# 8ChannelIoTLEDDriver.net
KiCad netlist of a schematic drawn in EAGLE
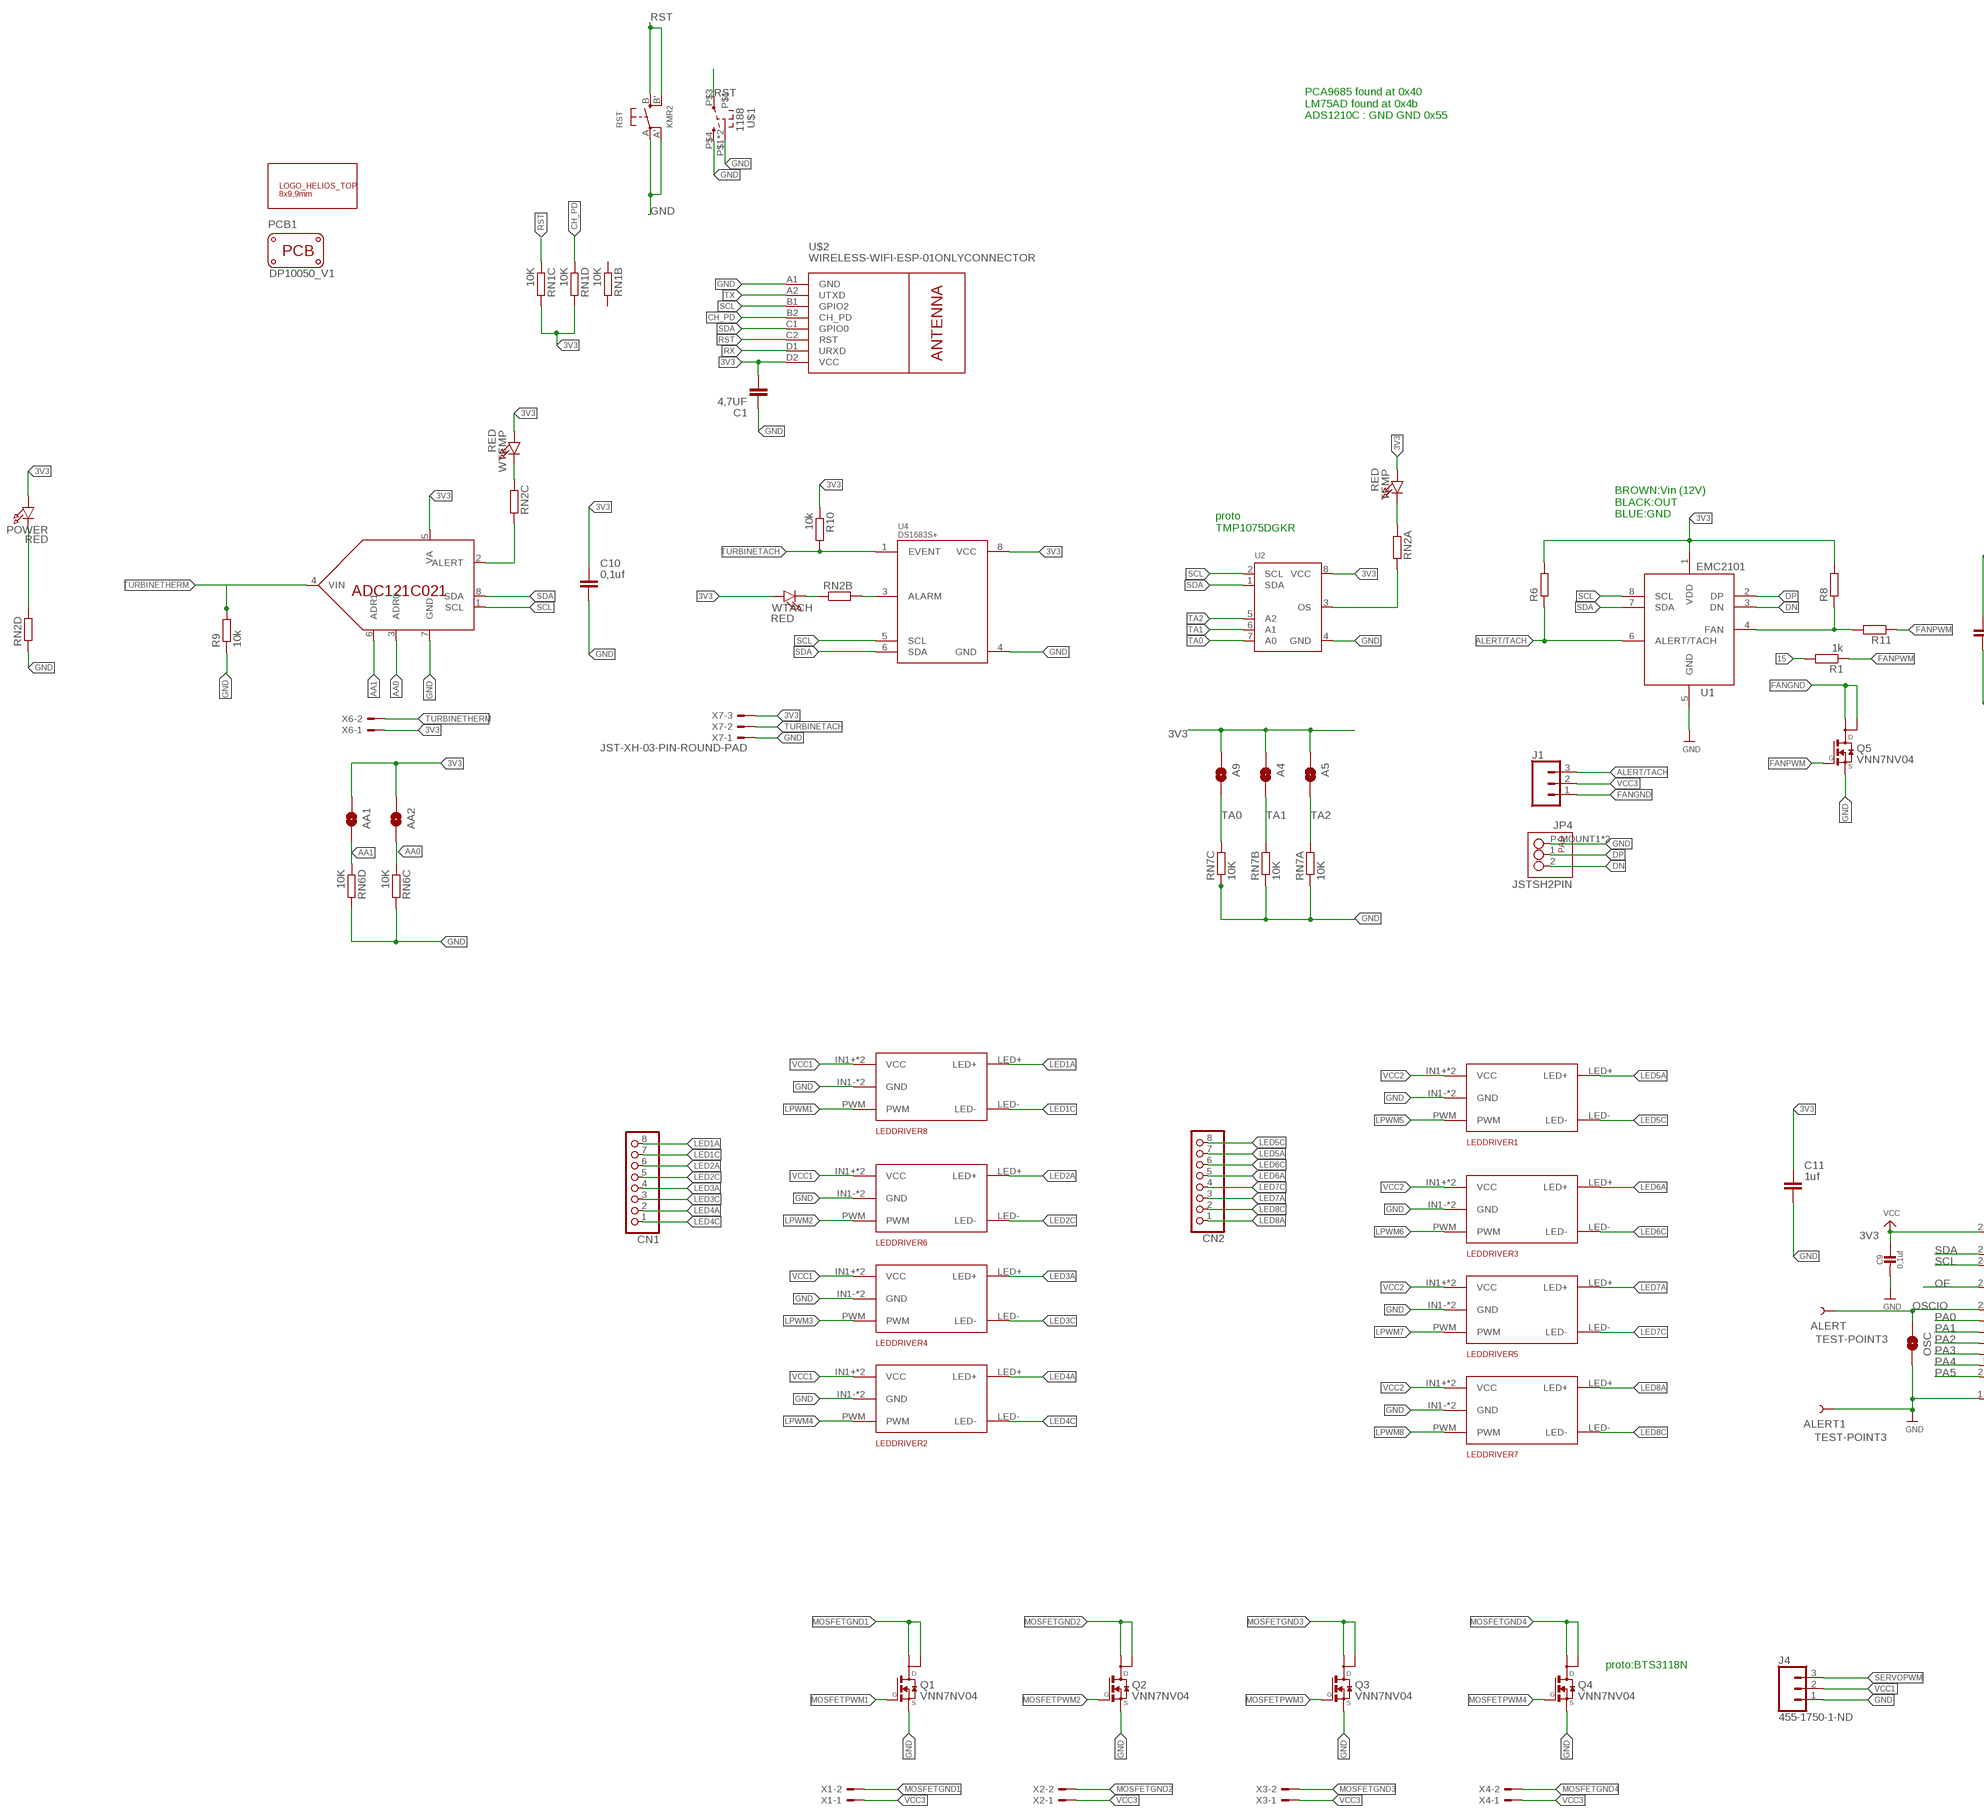
[diagram p0: schematic, sheet 1, part 1 of 2]
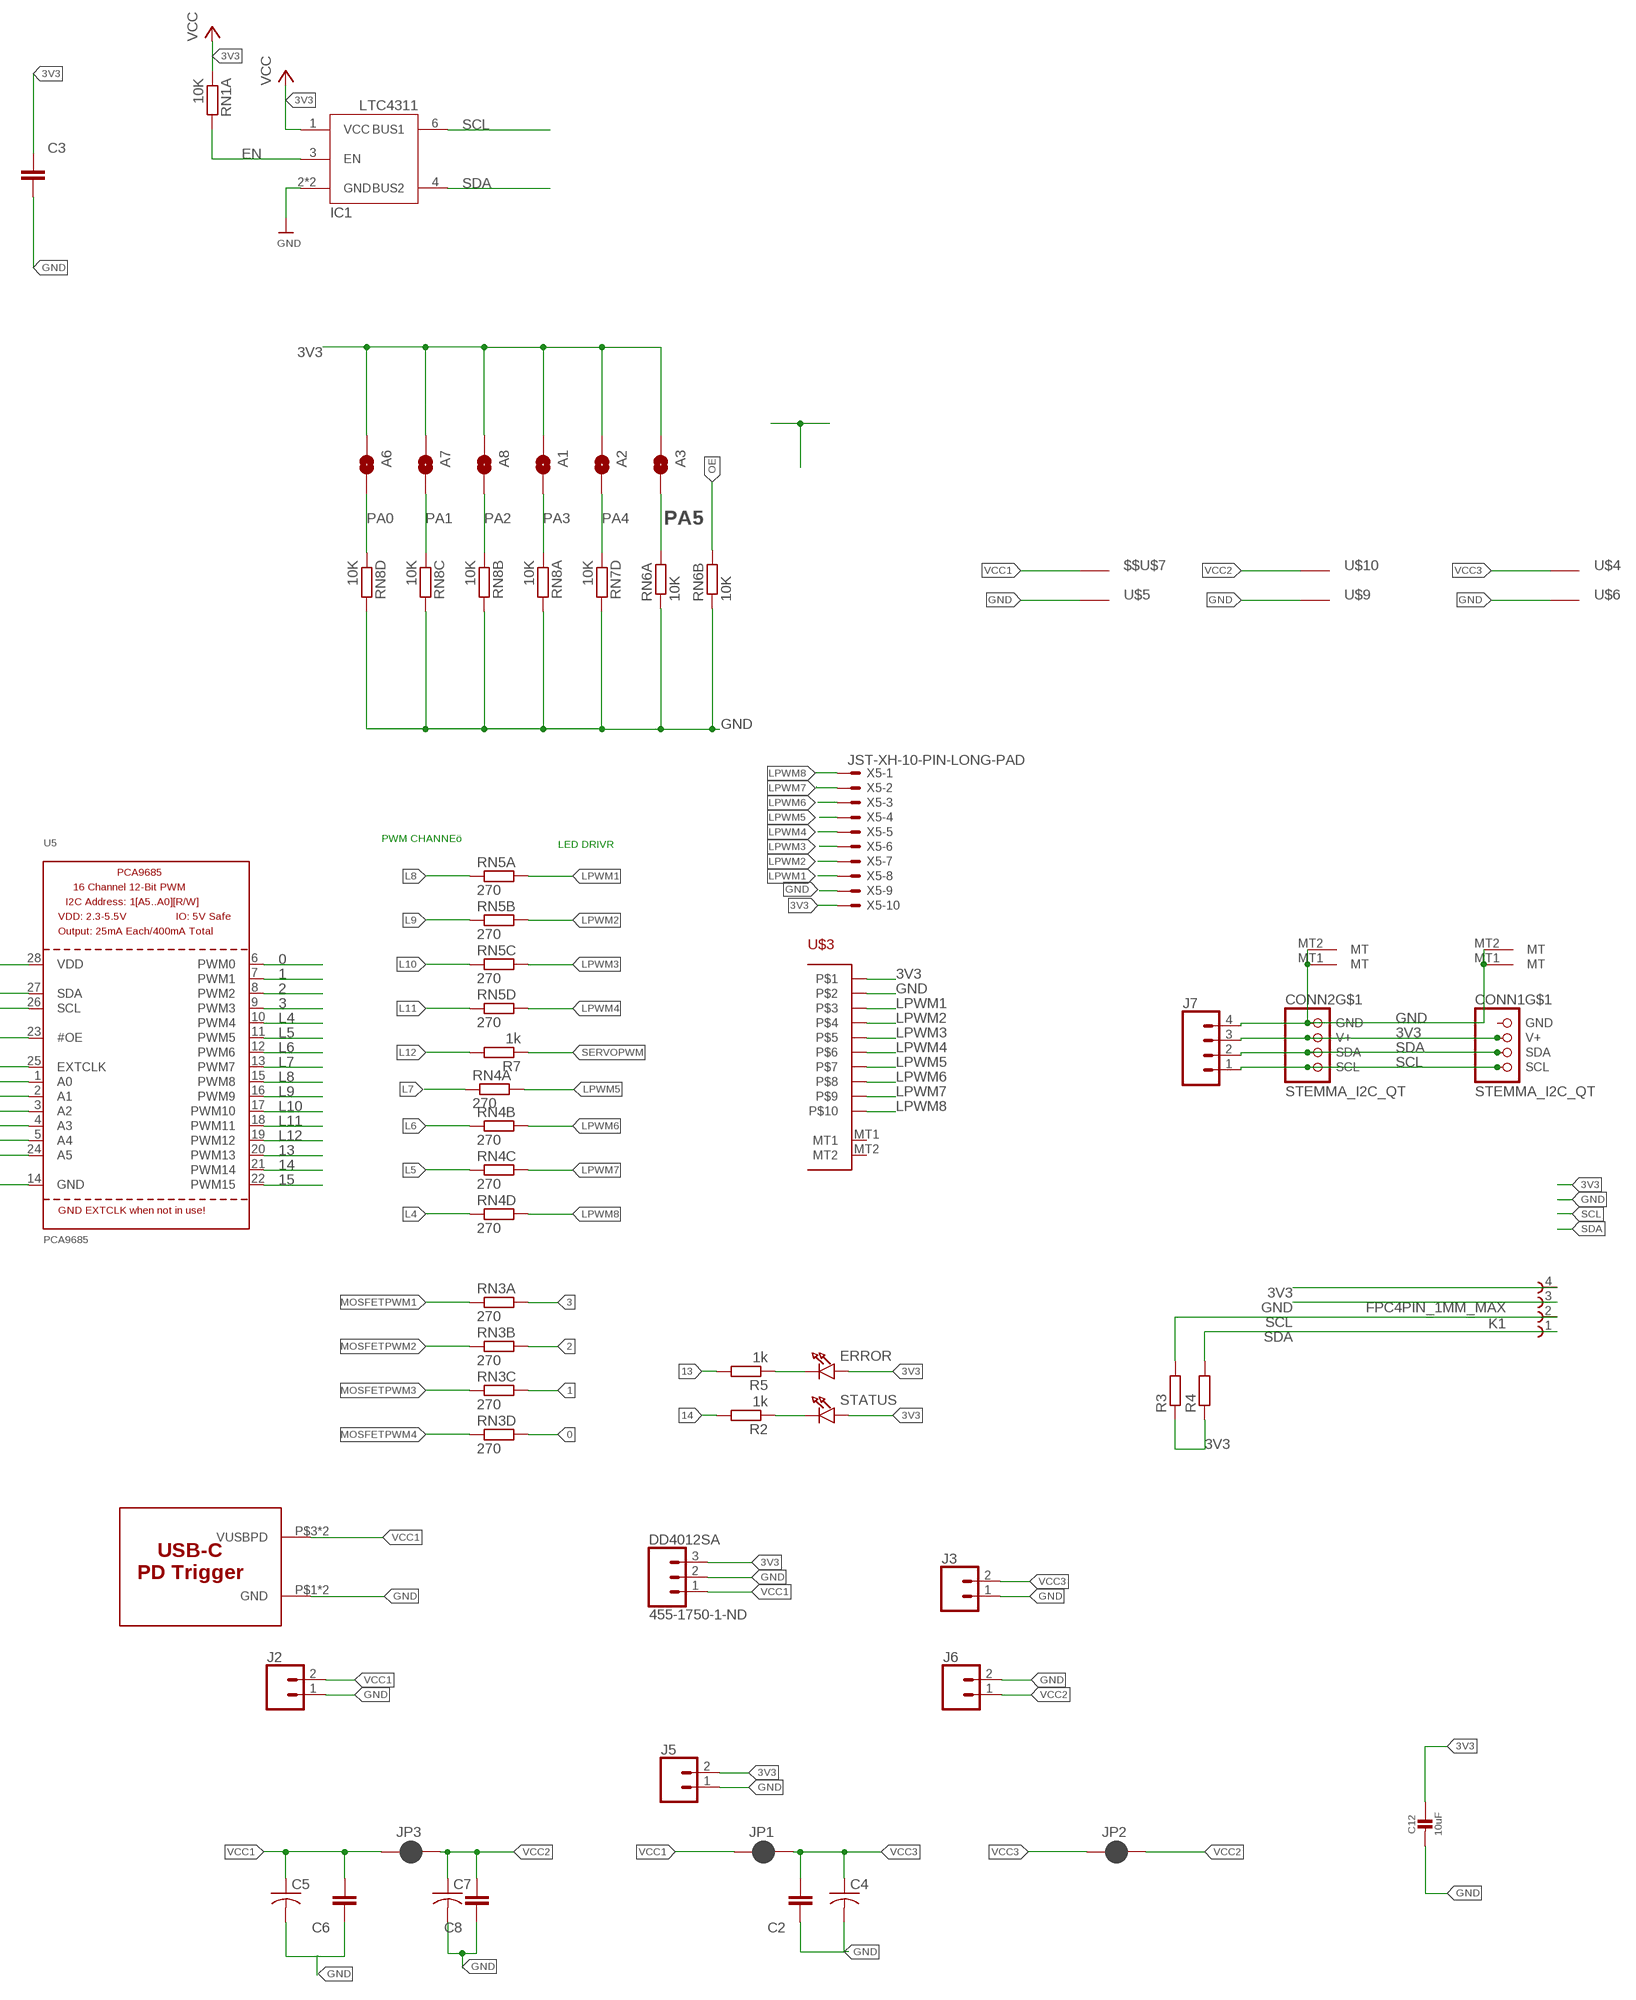
[diagram p1: schematic, sheet 1, part 2 of 2]

(export (version "E")
  (design (tool "Eeschema 10.0.6"))
  (components
    (comp (ref "$$U$7")
      (value "TESTHOOK")
      (footprint "eagle-import:TESTHOOK")
      (libsource (lib "eagle-import") (part "TESTHOOK"))
    )
    (comp (ref "A1")
      (value "JUMPER-SMT_2_NO_SILK")
      (footprint "eagle-import:SMT-JUMPER_2_NO_SILK")
      (libsource (lib "eagle-import") (part "JUMPER-SMT_2_NO_SILK"))
    )
    (comp (ref "A2")
      (value "JUMPER-SMT_2_NO_SILK")
      (footprint "eagle-import:SMT-JUMPER_2_NO_SILK")
      (libsource (lib "eagle-import") (part "JUMPER-SMT_2_NO_SILK"))
    )
    (comp (ref "A3")
      (value "JUMPER-SMT_2_NO_SILK")
      (footprint "eagle-import:SMT-JUMPER_2_NO_SILK")
      (libsource (lib "eagle-import") (part "JUMPER-SMT_2_NO_SILK"))
    )
    (comp (ref "A4")
      (value "JUMPER-SMT_2_NO_SILK")
      (footprint "eagle-import:SMT-JUMPER_2_NO_SILK")
      (libsource (lib "eagle-import") (part "JUMPER-SMT_2_NO_SILK"))
    )
    (comp (ref "A5")
      (value "JUMPER-SMT_2_NO_SILK")
      (footprint "eagle-import:SMT-JUMPER_2_NO_SILK")
      (libsource (lib "eagle-import") (part "JUMPER-SMT_2_NO_SILK"))
    )
    (comp (ref "A6")
      (value "JUMPER-SMT_2_NO_SILK")
      (footprint "eagle-import:SMT-JUMPER_2_NO_SILK")
      (libsource (lib "eagle-import") (part "JUMPER-SMT_2_NO_SILK"))
    )
    (comp (ref "A7")
      (value "JUMPER-SMT_2_NO_SILK")
      (footprint "eagle-import:SMT-JUMPER_2_NO_SILK")
      (libsource (lib "eagle-import") (part "JUMPER-SMT_2_NO_SILK"))
    )
    (comp (ref "A8")
      (value "JUMPER-SMT_2_NO_SILK")
      (footprint "eagle-import:SMT-JUMPER_2_NO_SILK")
      (libsource (lib "eagle-import") (part "JUMPER-SMT_2_NO_SILK"))
    )
    (comp (ref "A9")
      (value "JUMPER-SMT_2_NO_SILK")
      (footprint "eagle-import:SMT-JUMPER_2_NO_SILK")
      (libsource (lib "eagle-import") (part "JUMPER-SMT_2_NO_SILK"))
    )
    (comp (ref "AA1")
      (value "JUMPER-SMT_2_NO_SILK")
      (footprint "eagle-import:SMT-JUMPER_2_NO_SILK")
      (libsource (lib "eagle-import") (part "JUMPER-SMT_2_NO_SILK"))
    )
    (comp (ref "AA2")
      (value "JUMPER-SMT_2_NO_SILK")
      (footprint "eagle-import:SMT-JUMPER_2_NO_SILK")
      (libsource (lib "eagle-import") (part "JUMPER-SMT_2_NO_SILK"))
    )
    (comp (ref "ALERT")
      (value "TEST-POINT3")
      (footprint "eagle-import:PAD.03X.03")
      (libsource (lib "eagle-import") (part "TEST-POINT3"))
    )
    (comp (ref "ALERT1")
      (value "TEST-POINT3")
      (footprint "eagle-import:PAD.03X.03")
      (libsource (lib "eagle-import") (part "TEST-POINT3"))
    )
    (comp (ref "C1")
      (value "4,7UF")
      (footprint "eagle-import:C805")
      (libsource (lib "eagle-import") (part "CAPACITOR_NPOL-0805"))
    )
    (comp (ref "C2")
      (value "CAPACITOR_NPOL-0805")
      (footprint "eagle-import:C805")
      (libsource (lib "eagle-import") (part "CAPACITOR_NPOL-0805"))
    )
    (comp (ref "C3")
      (value "CAPACITOR_NPOL-0805")
      (footprint "eagle-import:C805")
      (libsource (lib "eagle-import") (part "CAPACITOR_NPOL-0805"))
    )
    (comp (ref "C4")
      (value "C-USC1210")
      (footprint "eagle-import:C1210")
      (libsource (lib "eagle-import") (part "C-USC1210"))
    )
    (comp (ref "C5")
      (value "C-USC1210")
      (footprint "eagle-import:C1210")
      (libsource (lib "eagle-import") (part "C-USC1210"))
    )
    (comp (ref "C6")
      (value "CAPACITOR_NPOL-0805")
      (footprint "eagle-import:C805")
      (libsource (lib "eagle-import") (part "CAPACITOR_NPOL-0805"))
    )
    (comp (ref "C7")
      (value "C-USC1210")
      (footprint "eagle-import:C1210")
      (libsource (lib "eagle-import") (part "C-USC1210"))
    )
    (comp (ref "C8")
      (value "CAPACITOR_NPOL-0805")
      (footprint "eagle-import:C805")
      (libsource (lib "eagle-import") (part "CAPACITOR_NPOL-0805"))
    )
    (comp (ref "C9")
      (value "0,1uf")
      (footprint "eagle-import:0805-NO")
      (libsource (lib "eagle-import") (part "CAP_CERAMIC0805-NOOUTLINE"))
    )
    (comp (ref "C10")
      (value "0,1uf")
      (footprint "eagle-import:C805")
      (libsource (lib "eagle-import") (part "CAPACITOR_NPOL-0805"))
    )
    (comp (ref "C11")
      (value "1uf")
      (footprint "eagle-import:C805")
      (libsource (lib "eagle-import") (part "CAPACITOR_NPOL-0805"))
    )
    (comp (ref "C12")
      (value "10uF")
      (footprint "eagle-import:0805-NO")
      (libsource (lib "eagle-import") (part "CAP_CERAMIC0805-NOOUTLINE"))
    )
    (comp (ref "CN1")
      (value "JST_8PIN")
      (footprint "eagle-import:JSTPH8")
      (libsource (lib "eagle-import") (part "JST_8PIN"))
    )
    (comp (ref "CN2")
      (value "JST_8PIN")
      (footprint "eagle-import:JSTPH8")
      (libsource (lib "eagle-import") (part "JST_8PIN"))
    )
    (comp (ref "CONN1")
      (value "STEMMA_I2C_QT")
      (footprint "eagle-import:JST_SH4")
      (libsource (lib "eagle-import") (part "STEMMA_I2C_QT"))
    )
    (comp (ref "CONN2")
      (value "STEMMA_I2C_QT")
      (footprint "eagle-import:JST_SH4")
      (libsource (lib "eagle-import") (part "STEMMA_I2C_QT"))
    )
    (comp (ref "DD4012SA")
      (value "455-1750-1-ND")
      (footprint "eagle-import:1X03")
      (libsource (lib "eagle-import") (part "CONN_03"))
    )
    (comp (ref "ERROR")
      (value "RED")
      (footprint "eagle-import:CHIPLED_0805")
      (libsource (lib "eagle-import") (part "LED0805"))
    )
    (comp (ref "IC1")
      (value "LTC4311_SC70")
      (footprint "eagle-import:SC70-6L")
      (libsource (lib "eagle-import") (part "LTC4311_SC70"))
    )
    (comp (ref "J1")
      (value "CONN_03POLAR")
      (footprint "eagle-import:MOLEX-1X3")
      (libsource (lib "eagle-import") (part "CONN_03POLAR"))
    )
    (comp (ref "J2")
      (value "CONN_02POLAR")
      (footprint "eagle-import:MOLEX-1X2")
      (libsource (lib "eagle-import") (part "CONN_02POLAR"))
    )
    (comp (ref "J3")
      (value "CONN_02POLAR")
      (footprint "eagle-import:MOLEX-1X2")
      (libsource (lib "eagle-import") (part "CONN_02POLAR"))
    )
    (comp (ref "J4")
      (value "455-1750-1-ND")
      (footprint "eagle-import:1X03")
      (libsource (lib "eagle-import") (part "CONN_03"))
    )
    (comp (ref "J5")
      (value "CONN_02POLAR")
      (footprint "eagle-import:MOLEX-1X2")
      (libsource (lib "eagle-import") (part "CONN_02POLAR"))
    )
    (comp (ref "J6")
      (value "CONN_023.5MM")
      (footprint "eagle-import:SCREWTERMINAL-3.5MM-2")
      (libsource (lib "eagle-import") (part "CONN_023.5MM"))
    )
    (comp (ref "J7")
      (value "CONN_04JST-PH-4-1.0MM")
      (footprint "eagle-import:JST-4-SMD-VERT-1.0MM")
      (libsource (lib "eagle-import") (part "CONN_04JST-PH-4-1.0MM"))
    )
    (comp (ref "JP1")
      (value "JUMPER-SMT_2_NC_PASTE_SILK")
      (footprint "eagle-import:SMT-JUMPER_2_NC_PASTE_SILK")
      (libsource (lib "eagle-import") (part "JUMPER-SMT_2_NC_PASTE_SILK"))
    )
    (comp (ref "JP2")
      (value "JUMPER-SMT_2_NC_PASTE_SILK")
      (footprint "eagle-import:SMT-JUMPER_2_NC_PASTE_SILK")
      (libsource (lib "eagle-import") (part "JUMPER-SMT_2_NC_PASTE_SILK"))
    )
    (comp (ref "JP3")
      (value "JUMPER-SMT_2_NC_PASTE_SILK")
      (footprint "eagle-import:SMT-JUMPER_2_NC_PASTE_SILK")
      (libsource (lib "eagle-import") (part "JUMPER-SMT_2_NC_PASTE_SILK"))
    )
    (comp (ref "JP4")
      (value "JSTSH2PIN")
      (footprint "eagle-import:SM02B-SRSS-TB")
      (libsource (lib "eagle-import") (part "JSTSH2PIN"))
    )
    (comp (ref "K1")
      (value "FPC4PIN_1MM_MAX")
      (footprint "eagle-import:FPC_CONN_DOC_4PIN_ENLARGED")
      (libsource (lib "eagle-import") (part "FPC4PIN_1MM_MAX"))
    )
    (comp (ref "LEDDRIVER1")
      (value "LEDDRIVERPT4115LONG")
      (footprint "eagle-import:7PINLONGLEDDRIVER")
      (libsource (lib "eagle-import") (part "LEDDRIVERPT4115LONG"))
    )
    (comp (ref "LEDDRIVER2")
      (value "LEDDRIVERPT4115LONG")
      (footprint "eagle-import:7PINLONGLEDDRIVER")
      (libsource (lib "eagle-import") (part "LEDDRIVERPT4115LONG"))
    )
    (comp (ref "LEDDRIVER3")
      (value "LEDDRIVERPT4115LONG")
      (footprint "eagle-import:7PINLONGLEDDRIVER")
      (libsource (lib "eagle-import") (part "LEDDRIVERPT4115LONG"))
    )
    (comp (ref "LEDDRIVER4")
      (value "LEDDRIVERPT4115LONG")
      (footprint "eagle-import:7PINLONGLEDDRIVER")
      (libsource (lib "eagle-import") (part "LEDDRIVERPT4115LONG"))
    )
    (comp (ref "LEDDRIVER5")
      (value "LEDDRIVERPT4115LONG")
      (footprint "eagle-import:7PINLONGLEDDRIVER")
      (libsource (lib "eagle-import") (part "LEDDRIVERPT4115LONG"))
    )
    (comp (ref "LEDDRIVER6")
      (value "LEDDRIVERPT4115LONG")
      (footprint "eagle-import:7PINLONGLEDDRIVER")
      (libsource (lib "eagle-import") (part "LEDDRIVERPT4115LONG"))
    )
    (comp (ref "LEDDRIVER7")
      (value "LEDDRIVERPT4115LONG")
      (footprint "eagle-import:7PINLONGLEDDRIVER")
      (libsource (lib "eagle-import") (part "LEDDRIVERPT4115LONG"))
    )
    (comp (ref "LEDDRIVER8")
      (value "LEDDRIVERPT4115LONG")
      (footprint "eagle-import:7PINLONGLEDDRIVER")
      (libsource (lib "eagle-import") (part "LEDDRIVERPT4115LONG"))
    )
    (comp (ref "OSC")
      (value "JUMPER-SMT_2_NO_SILK")
      (footprint "eagle-import:SMT-JUMPER_2_NO_SILK")
      (libsource (lib "eagle-import") (part "JUMPER-SMT_2_NO_SILK"))
    )
    (comp (ref "PCB1")
      (value "PCB_DP_RECTANGLE-50X100")
      (footprint "eagle-import:DP10050_V1")
      (fields (field (name "PCB_SIZE") "DP10050_V1"))
      (libsource (lib "eagle-import") (part "PCB_DP_RECTANGLE-50X100"))
    )
    (comp (ref "POWER")
      (value "RED")
      (footprint "eagle-import:CHIPLED_0805")
      (libsource (lib "eagle-import") (part "LED0805"))
    )
    (comp (ref "Q1")
      (value "VNN7NV04")
      (footprint "eagle-import:SOT223")
      (fields (field (name "MF") "STMicroelectronics"))
      (libsource (lib "eagle-import") (part "VNN7NV04"))
    )
    (comp (ref "Q2")
      (value "VNN7NV04")
      (footprint "eagle-import:SOT223")
      (fields (field (name "MF") "STMicroelectronics"))
      (libsource (lib "eagle-import") (part "VNN7NV04"))
    )
    (comp (ref "Q3")
      (value "VNN7NV04")
      (footprint "eagle-import:SOT223")
      (fields (field (name "MF") "STMicroelectronics"))
      (libsource (lib "eagle-import") (part "VNN7NV04"))
    )
    (comp (ref "Q4")
      (value "VNN7NV04")
      (footprint "eagle-import:SOT223")
      (fields (field (name "MF") "STMicroelectronics"))
      (libsource (lib "eagle-import") (part "VNN7NV04"))
    )
    (comp (ref "Q5")
      (value "VNN7NV04")
      (footprint "eagle-import:SOT223")
      (fields (field (name "MF") "STMicroelectronics"))
      (libsource (lib "eagle-import") (part "VNN7NV04"))
    )
    (comp (ref "R1")
      (value "1k")
      (footprint "eagle-import:R805")
      (libsource (lib "eagle-import") (part "RESISTOR-0805R805"))
    )
    (comp (ref "R2")
      (value "1k")
      (footprint "eagle-import:R805")
      (libsource (lib "eagle-import") (part "RESISTOR-0805R805"))
    )
    (comp (ref "R3")
      (value "RESISTORR805-0805")
      (footprint "eagle-import:R805")
      (libsource (lib "eagle-import") (part "RESISTOR-0805R805"))
    )
    (comp (ref "R4")
      (value "RESISTORR805-0805")
      (footprint "eagle-import:R805")
      (libsource (lib "eagle-import") (part "RESISTOR-0805R805"))
    )
    (comp (ref "R5")
      (value "1k")
      (footprint "eagle-import:R805")
      (libsource (lib "eagle-import") (part "RESISTOR-0805R805"))
    )
    (comp (ref "R6")
      (value "RESISTORR805-0805")
      (footprint "eagle-import:R805")
      (libsource (lib "eagle-import") (part "RESISTOR-0805R805"))
    )
    (comp (ref "R7")
      (value "1k")
      (footprint "eagle-import:R805")
      (libsource (lib "eagle-import") (part "RESISTOR-0805R805"))
    )
    (comp (ref "R8")
      (value "RESISTORR805-0805")
      (footprint "eagle-import:R805")
      (libsource (lib "eagle-import") (part "RESISTOR-0805R805"))
    )
    (comp (ref "R9")
      (value "10k")
      (footprint "eagle-import:R805")
      (libsource (lib "eagle-import") (part "RESISTOR-0805R805"))
    )
    (comp (ref "R10")
      (value "10k")
      (footprint "eagle-import:R805")
      (libsource (lib "eagle-import") (part "RESISTOR-0805R805"))
    )
    (comp (ref "R11")
      (value "RESISTORR805-0805")
      (footprint "eagle-import:R805")
      (libsource (lib "eagle-import") (part "RESISTOR-0805R805"))
    )
    (comp (ref "RN1")
      (value "10K")
      (footprint "eagle-import:RN8P-4R-CRA06S")
      (libsource (lib "eagle-import") (part "RESISTOR_ARRAY_4"))
    )
    (comp (ref "RN2")
      (value "RESISTOR_ARRAY_4")
      (footprint "eagle-import:RN8P-4R-CRA06S")
      (libsource (lib "eagle-import") (part "RESISTOR_ARRAY_4"))
    )
    (comp (ref "RN3")
      (value "270")
      (footprint "eagle-import:RN8P-4R-CRA06S")
      (libsource (lib "eagle-import") (part "RESISTOR_ARRAY_4"))
    )
    (comp (ref "RN4")
      (value "270")
      (footprint "eagle-import:RN8P-4R-CRA06S")
      (libsource (lib "eagle-import") (part "RESISTOR_ARRAY_4"))
    )
    (comp (ref "RN5")
      (value "270")
      (footprint "eagle-import:RN8P-4R-CRA06S")
      (libsource (lib "eagle-import") (part "RESISTOR_ARRAY_4"))
    )
    (comp (ref "RN6")
      (value "10K")
      (footprint "eagle-import:RN8P-4R-CRA06S")
      (libsource (lib "eagle-import") (part "RESISTOR_ARRAY_4"))
    )
    (comp (ref "RN7")
      (value "10K")
      (footprint "eagle-import:RN8P-4R-CRA06S")
      (libsource (lib "eagle-import") (part "RESISTOR_ARRAY_4"))
    )
    (comp (ref "RN8")
      (value "10K")
      (footprint "eagle-import:RN8P-4R-CRA06S")
      (libsource (lib "eagle-import") (part "RESISTOR_ARRAY_4"))
    )
    (comp (ref "RST")
      (value "KMR2")
      (footprint "eagle-import:BTN_KMR2_4.6X2.8")
      (libsource (lib "eagle-import") (part "SWITCH_TACT_SMT4.6X2.8"))
    )
    (comp (ref "STATUS")
      (value "RED")
      (footprint "eagle-import:CHIPLED_0805")
      (libsource (lib "eagle-import") (part "LED0805"))
    )
    (comp (ref "TEMP")
      (value "RED")
      (footprint "eagle-import:CHIPLED_0805")
      (libsource (lib "eagle-import") (part "LED0805"))
    )
    (comp (ref "U$1")
      (value "1188")
      (footprint "eagle-import:1188")
      (libsource (lib "eagle-import") (part "1188"))
    )
    (comp (ref "U$2")
      (value "WIRELESS-WIFI-ESP-01ONLYCONNECTOR")
      (footprint "eagle-import:WIRELESS-WIFI-ESP-01-ONLYBOTTOM")
      (libsource (lib "eagle-import") (part "WIRELESS-WIFI-ESP-01ONLYCONNECTOR"))
    )
    (comp (ref "U$3")
      (value "FPC-1.0X10")
      (footprint "eagle-import:FPC_1.0X10")
      (libsource (lib "eagle-import") (part "FPC-1.0X10"))
    )
    (comp (ref "U$4")
      (value "TESTHOOK")
      (footprint "eagle-import:TESTHOOK")
      (libsource (lib "eagle-import") (part "TESTHOOK"))
    )
    (comp (ref "U$5")
      (value "TESTHOOK")
      (footprint "eagle-import:TESTHOOK")
      (libsource (lib "eagle-import") (part "TESTHOOK"))
    )
    (comp (ref "U$6")
      (value "TESTHOOK")
      (footprint "eagle-import:TESTHOOK")
      (libsource (lib "eagle-import") (part "TESTHOOK"))
    )
    (comp (ref "U$8")
      (value "USB_PD_TRIGGER")
      (footprint "eagle-import:USB-PDTRIGGER")
      (libsource (lib "eagle-import") (part "USB_PD_TRIGGER"))
    )
    (comp (ref "U$9")
      (value "TESTHOOK")
      (footprint "eagle-import:TESTHOOK")
      (libsource (lib "eagle-import") (part "TESTHOOK"))
    )
    (comp (ref "U$10")
      (value "TESTHOOK")
      (footprint "eagle-import:TESTHOOK")
      (libsource (lib "eagle-import") (part "TESTHOOK"))
    )
    (comp (ref "U$11")
      (value "LOGOTOPHELIOS")
      (footprint "eagle-import:LOGOTOPHELIOS")
      (libsource (lib "eagle-import") (part "LOGOTOPHELIOS"))
    )
    (comp (ref "U1")
      (value "EMC2101-AZCL")
      (footprint "eagle-import:MSOP8_0.65MM")
      (libsource (lib "eagle-import") (part "EMC2101-AZCL"))
    )
    (comp (ref "U2")
      (value "TEMP_LM75B")
      (footprint "eagle-import:TSSOP8")
      (libsource (lib "eagle-import") (part "TEMP_LM75B"))
    )
    (comp (ref "U3")
      (value "ADC121C021")
      (footprint "eagle-import:MSOP08")
      (libsource (lib "eagle-import") (part "ADC121C021"))
    )
    (comp (ref "U4")
      (value "DS1683S+")
      (footprint "eagle-import:SOIC8-N_MC")
      (libsource (lib "eagle-import") (part "DS1683S+"))
    )
    (comp (ref "U5")
      (value "PCA9685")
      (footprint "eagle-import:TSSOP28")
      (libsource (lib "eagle-import") (part "PCA9685"))
    )
    (comp (ref "WTACH")
      (value "RED")
      (footprint "eagle-import:CHIPLED_0805")
      (libsource (lib "eagle-import") (part "LED0805"))
    )
    (comp (ref "WTEMP")
      (value "RED")
      (footprint "eagle-import:CHIPLED_0805")
      (libsource (lib "eagle-import") (part "LED0805"))
    )
    (comp (ref "X1")
      (value "JST-XH-02-PIN-ROUND-PAD")
      (footprint "eagle-import:JST-XH-02-PACKAGE-ROUND-PAD")
      (libsource (lib "eagle-import") (part "JST-XH-02-PIN-ROUND-PAD"))
    )
    (comp (ref "X2")
      (value "JST-XH-02-PIN-ROUND-PAD")
      (footprint "eagle-import:JST-XH-02-PACKAGE-ROUND-PAD")
      (libsource (lib "eagle-import") (part "JST-XH-02-PIN-ROUND-PAD"))
    )
    (comp (ref "X3")
      (value "JST-XH-02-PIN-ROUND-PAD")
      (footprint "eagle-import:JST-XH-02-PACKAGE-ROUND-PAD")
      (libsource (lib "eagle-import") (part "JST-XH-02-PIN-ROUND-PAD"))
    )
    (comp (ref "X4")
      (value "JST-XH-02-PIN-ROUND-PAD")
      (footprint "eagle-import:JST-XH-02-PACKAGE-ROUND-PAD")
      (libsource (lib "eagle-import") (part "JST-XH-02-PIN-ROUND-PAD"))
    )
    (comp (ref "X5")
      (value "JST-XH-10-PIN-LONG-PAD")
      (footprint "eagle-import:JST-XH-10-PACKAGE-LONG-PAD")
      (libsource (lib "eagle-import") (part "JST-XH-10-PIN-LONG-PAD"))
    )
    (comp (ref "X6")
      (value "JST-XH-02-PIN-ROUND-PAD")
      (footprint "eagle-import:JST-XH-02-PACKAGE-ROUND-PAD")
      (libsource (lib "eagle-import") (part "JST-XH-02-PIN-ROUND-PAD"))
    )
    (comp (ref "X7")
      (value "JST-XH-03-PIN-ROUND-PAD")
      (footprint "eagle-import:JST-XH-03-PACKAGE-ROUND-PAD")
      (libsource (lib "eagle-import") (part "JST-XH-03-PIN-ROUND-PAD"))
    )
  )
  (nets
    (net (code "1") (name "/EN") (class "Default")
      (node (ref "IC1") (pin "3") (pinfunction "EN_3") (pintype "input"))
      (node (ref "RN1") (pin "8") (pinfunction "2_8") (pintype "passive"))
    )
    (net (code "2") (name "/OSCIO") (class "Default")
      (node (ref "ALERT") (pin "P$1") (pinfunction "1_P$1") (pintype "bidirectional"))
      (node (ref "OSC") (pin "1") (pinfunction "1_1") (pintype "passive"))
      (node (ref "U5") (pin "25") (pinfunction "EXTCLK_25") (pintype "input"))
    )
    (net (code "3") (name "/PA0") (class "Default")
      (node (ref "A6") (pin "2") (pinfunction "2_2") (pintype "passive"))
      (node (ref "RN8") (pin "4") (pinfunction "1_4") (pintype "passive"))
      (node (ref "U5") (pin "1") (pinfunction "A0_1") (pintype "bidirectional"))
    )
    (net (code "4") (name "/PA1") (class "Default")
      (node (ref "A7") (pin "2") (pinfunction "2_2") (pintype "passive"))
      (node (ref "RN8") (pin "3") (pinfunction "1_3") (pintype "passive"))
      (node (ref "U5") (pin "2") (pinfunction "A1_2") (pintype "bidirectional"))
    )
    (net (code "5") (name "/PA2") (class "Default")
      (node (ref "A8") (pin "2") (pinfunction "2_2") (pintype "passive"))
      (node (ref "RN8") (pin "2") (pinfunction "1_2") (pintype "passive"))
      (node (ref "U5") (pin "3") (pinfunction "A2_3") (pintype "bidirectional"))
    )
    (net (code "6") (name "/PA3") (class "Default")
      (node (ref "A1") (pin "2") (pinfunction "2_2") (pintype "passive"))
      (node (ref "RN8") (pin "1") (pinfunction "1_1") (pintype "passive"))
      (node (ref "U5") (pin "4") (pinfunction "A3_4") (pintype "bidirectional"))
    )
    (net (code "7") (name "/PA4") (class "Default")
      (node (ref "A2") (pin "2") (pinfunction "2_2") (pintype "passive"))
      (node (ref "RN7") (pin "4") (pinfunction "1_4") (pintype "passive"))
      (node (ref "U5") (pin "5") (pinfunction "A4_5") (pintype "bidirectional"))
    )
    (net (code "8") (name "/PA5") (class "Default")
      (node (ref "A3") (pin "2") (pinfunction "2_2") (pintype "passive"))
      (node (ref "RN6") (pin "8") (pinfunction "2_8") (pintype "passive"))
      (node (ref "U5") (pin "24") (pinfunction "A5_24") (pintype "bidirectional"))
    )
    (net (code "9") (name "0") (class "Default")
      (node (ref "RN3") (pin "5") (pinfunction "2_5") (pintype "passive"))
      (node (ref "U5") (pin "6") (pinfunction "PWM0_6") (pintype "output"))
    )
    (net (code "10") (name "1") (class "Default")
      (node (ref "RN3") (pin "6") (pinfunction "2_6") (pintype "passive"))
      (node (ref "U5") (pin "7") (pinfunction "PWM1_7") (pintype "output"))
    )
    (net (code "11") (name "2") (class "Default")
      (node (ref "RN3") (pin "7") (pinfunction "2_7") (pintype "passive"))
      (node (ref "U5") (pin "8") (pinfunction "PWM2_8") (pintype "output"))
    )
    (net (code "12") (name "3") (class "Default")
      (node (ref "RN3") (pin "8") (pinfunction "2_8") (pintype "passive"))
      (node (ref "U5") (pin "9") (pinfunction "PWM3_9") (pintype "output"))
    )
    (net (code "13") (name "3V3") (class "Default")
      (node (ref "A1") (pin "1") (pinfunction "1_1") (pintype "passive"))
      (node (ref "A2") (pin "1") (pinfunction "1_1") (pintype "passive"))
      (node (ref "A3") (pin "1") (pinfunction "1_1") (pintype "passive"))
      (node (ref "A4") (pin "1") (pinfunction "1_1") (pintype "passive"))
      (node (ref "A5") (pin "1") (pinfunction "1_1") (pintype "passive"))
      (node (ref "A6") (pin "1") (pinfunction "1_1") (pintype "passive"))
      (node (ref "A7") (pin "1") (pinfunction "1_1") (pintype "passive"))
      (node (ref "A8") (pin "1") (pinfunction "1_1") (pintype "passive"))
      (node (ref "A9") (pin "1") (pinfunction "1_1") (pintype "passive"))
      (node (ref "AA1") (pin "1") (pinfunction "1_1") (pintype "passive"))
      (node (ref "AA2") (pin "1") (pinfunction "1_1") (pintype "passive"))
      (node (ref "C1") (pin "2") (pinfunction "2_2") (pintype "passive"))
      (node (ref "C10") (pin "1") (pinfunction "1_1") (pintype "passive"))
      (node (ref "C11") (pin "1") (pinfunction "1_1") (pintype "passive"))
      (node (ref "C12") (pin "1") (pinfunction "1_1") (pintype "passive"))
      (node (ref "C3") (pin "1") (pinfunction "1_1") (pintype "passive"))
      (node (ref "C9") (pin "1") (pinfunction "1_1") (pintype "passive"))
      (node (ref "CONN1") (pin "2") (pinfunction "V+_2") (pintype "passive"))
      (node (ref "CONN2") (pin "2") (pinfunction "V+_2") (pintype "passive"))
      (node (ref "DD4012SA") (pin "3") (pinfunction "3_3") (pintype "passive"))
      (node (ref "ERROR") (pin "A") (pinfunction "A_A") (pintype "passive"))
      (node (ref "IC1") (pin "1") (pinfunction "VCC_1") (pintype "power_in"))
      (node (ref "J5") (pin "2") (pinfunction "2_2") (pintype "passive"))
      (node (ref "J7") (pin "3") (pinfunction "3_3") (pintype "passive"))
      (node (ref "K1") (pin "4") (pinfunction "4_4") (pintype "passive"))
      (node (ref "POWER") (pin "A") (pinfunction "A_A") (pintype "passive"))
      (node (ref "R10") (pin "1") (pinfunction "1_1") (pintype "passive"))
      (node (ref "R3") (pin "1") (pinfunction "1_1") (pintype "passive"))
      (node (ref "R4") (pin "1") (pinfunction "1_1") (pintype "passive"))
      (node (ref "R6") (pin "2") (pinfunction "2_2") (pintype "passive"))
      (node (ref "R8") (pin "2") (pinfunction "2_2") (pintype "passive"))
      (node (ref "RN1") (pin "1") (pinfunction "1_1") (pintype "passive"))
      (node (ref "RN1") (pin "5") (pinfunction "2_5") (pintype "passive"))
      (node (ref "RN1") (pin "6") (pinfunction "2_6") (pintype "passive"))
      (node (ref "STATUS") (pin "A") (pinfunction "A_A") (pintype "passive"))
      (node (ref "TEMP") (pin "A") (pinfunction "A_A") (pintype "passive"))
      (node (ref "U$2") (pin "D2") (pinfunction "VCC_D2") (pintype "power_in"))
      (node (ref "U$3") (pin "1") (pinfunction "P$1_1") (pintype "bidirectional"))
      (node (ref "U1") (pin "1") (pinfunction "VDD_1") (pintype "power_in"))
      (node (ref "U2") (pin "8") (pinfunction "VCC_8") (pintype "power_in"))
      (node (ref "U3") (pin "5") (pinfunction "VA_5") (pintype "power_in"))
      (node (ref "U4") (pin "8") (pinfunction "VCC_8") (pintype "bidirectional"))
      (node (ref "U5") (pin "28") (pinfunction "VDD_28") (pintype "power_in"))
      (node (ref "WTACH") (pin "A") (pinfunction "A_A") (pintype "passive"))
      (node (ref "WTEMP") (pin "A") (pinfunction "A_A") (pintype "passive"))
      (node (ref "X5") (pin "10") (pinfunction "S_10") (pintype "passive"))
      (node (ref "X6") (pin "1") (pinfunction "S_1") (pintype "passive"))
      (node (ref "X7") (pin "3") (pinfunction "S_3") (pintype "passive"))
    )
    (net (code "14") (name "13") (class "Default")
      (node (ref "R5") (pin "2") (pinfunction "2_2") (pintype "passive"))
      (node (ref "U5") (pin "20") (pinfunction "PWM13_20") (pintype "output"))
    )
    (net (code "15") (name "14") (class "Default")
      (node (ref "R2") (pin "2") (pinfunction "2_2") (pintype "passive"))
      (node (ref "U5") (pin "21") (pinfunction "PWM14_21") (pintype "output"))
    )
    (net (code "16") (name "15") (class "Default")
      (node (ref "R1") (pin "2") (pinfunction "2_2") (pintype "passive"))
      (node (ref "U5") (pin "22") (pinfunction "PWM15_22") (pintype "output"))
    )
    (net (code "17") (name "AA0") (class "Default")
      (node (ref "AA2") (pin "2") (pinfunction "2_2") (pintype "passive"))
      (node (ref "RN6") (pin "3") (pinfunction "1_3") (pintype "passive"))
      (node (ref "U3") (pin "3") (pinfunction "ADR0_3") (pintype "input"))
    )
    (net (code "18") (name "AA1") (class "Default")
      (node (ref "AA1") (pin "2") (pinfunction "2_2") (pintype "passive"))
      (node (ref "RN6") (pin "4") (pinfunction "1_4") (pintype "passive"))
      (node (ref "U3") (pin "6") (pinfunction "ADR1_6") (pintype "input"))
    )
    (net (code "19") (name "ALERT{slash}TACH") (class "Default")
      (node (ref "J1") (pin "3") (pinfunction "3_3") (pintype "passive"))
      (node (ref "R6") (pin "1") (pinfunction "1_1") (pintype "passive"))
      (node (ref "U1") (pin "6") (pinfunction "ALERT/TACH_6") (pintype "bidirectional"))
    )
    (net (code "20") (name "CH_PD") (class "Default")
      (node (ref "RN1") (pin "4") (pinfunction "1_4") (pintype "passive"))
      (node (ref "U$2") (pin "B2") (pinfunction "CH_PD_B2") (pintype "bidirectional"))
    )
    (net (code "21") (name "DN") (class "Default")
      (node (ref "JP4") (pin "2") (pinfunction "P$2_2") (pintype "bidirectional"))
      (node (ref "U1") (pin "3") (pinfunction "DN_3") (pintype "input"))
    )
    (net (code "22") (name "DP") (class "Default")
      (node (ref "JP4") (pin "1") (pinfunction "P$1_1") (pintype "bidirectional"))
      (node (ref "U1") (pin "2") (pinfunction "DP_2") (pintype "input"))
    )
    (net (code "23") (name "FANGND") (class "Default")
      (node (ref "J1") (pin "1") (pinfunction "1_1") (pintype "passive"))
      (node (ref "Q5") (pin "2") (pinfunction "D_2") (pintype "passive"))
      (node (ref "Q5") (pin "4") (pinfunction "D2_4") (pintype "passive"))
    )
    (net (code "24") (name "FANPWM") (class "Default")
      (node (ref "Q5") (pin "1") (pinfunction "G_1") (pintype "passive"))
      (node (ref "R1") (pin "1") (pinfunction "1_1") (pintype "passive"))
      (node (ref "R11") (pin "1") (pinfunction "1_1") (pintype "passive"))
    )
    (net (code "25") (name "GND") (class "Default")
      (node (ref "ALERT1") (pin "P$1") (pinfunction "1_P$1") (pintype "bidirectional"))
      (node (ref "C1") (pin "1") (pinfunction "1_1") (pintype "passive"))
      (node (ref "C10") (pin "2") (pinfunction "2_2") (pintype "passive"))
      (node (ref "C11") (pin "2") (pinfunction "2_2") (pintype "passive"))
      (node (ref "C12") (pin "2") (pinfunction "2_2") (pintype "passive"))
      (node (ref "C2") (pin "1") (pinfunction "1_1") (pintype "passive"))
      (node (ref "C3") (pin "2") (pinfunction "2_2") (pintype "passive"))
      (node (ref "C4") (pin "2") (pinfunction "2_2") (pintype "passive"))
      (node (ref "C5") (pin "2") (pinfunction "2_2") (pintype "passive"))
      (node (ref "C6") (pin "1") (pinfunction "1_1") (pintype "passive"))
      (node (ref "C7") (pin "2") (pinfunction "2_2") (pintype "passive"))
      (node (ref "C8") (pin "1") (pinfunction "1_1") (pintype "passive"))
      (node (ref "C9") (pin "2") (pinfunction "2_2") (pintype "passive"))
      (node (ref "CONN1") (pin "MT1") (pinfunction "MT_MT1") (pintype "bidirectional"))
      (node (ref "CONN1") (pin "MT2") (pinfunction "MT_MT2") (pintype "bidirectional"))
      (node (ref "CONN2") (pin "1") (pinfunction "GND_1") (pintype "passive"))
      (node (ref "CONN2") (pin "MT1") (pinfunction "MT_MT1") (pintype "bidirectional"))
      (node (ref "CONN2") (pin "MT2") (pinfunction "MT_MT2") (pintype "bidirectional"))
      (node (ref "DD4012SA") (pin "2") (pinfunction "2_2") (pintype "passive"))
      (node (ref "IC1") (pin "2") (pinfunction "GND_2") (pintype "power_in"))
      (node (ref "IC1") (pin "5") (pinfunction "GND_5") (pintype "power_in"))
      (node (ref "J2") (pin "1") (pinfunction "1_1") (pintype "passive"))
      (node (ref "J3") (pin "1") (pinfunction "1_1") (pintype "passive"))
      (node (ref "J4") (pin "1") (pinfunction "1_1") (pintype "passive"))
      (node (ref "J5") (pin "1") (pinfunction "1_1") (pintype "passive"))
      (node (ref "J6") (pin "2") (pinfunction "2_2") (pintype "passive"))
      (node (ref "J7") (pin "4") (pinfunction "4_4") (pintype "passive"))
      (node (ref "JP4") (pin "P-MOUNT1") (pinfunction "P$7_P-MOUNT1") (pintype "bidirectional"))
      (node (ref "JP4") (pin "P-MOUNT2") (pinfunction "P$7_P-MOUNT2") (pintype "bidirectional"))
      (node (ref "K1") (pin "3") (pinfunction "3_3") (pintype "passive"))
      (node (ref "LEDDRIVER1") (pin "IN1-") (pinfunction "GND_IN1-") (pintype "bidirectional"))
      (node (ref "LEDDRIVER1") (pin "IN2-") (pinfunction "GND_IN2-") (pintype "bidirectional"))
      (node (ref "LEDDRIVER2") (pin "IN1-") (pinfunction "GND_IN1-") (pintype "bidirectional"))
      (node (ref "LEDDRIVER2") (pin "IN2-") (pinfunction "GND_IN2-") (pintype "bidirectional"))
      (node (ref "LEDDRIVER3") (pin "IN1-") (pinfunction "GND_IN1-") (pintype "bidirectional"))
      (node (ref "LEDDRIVER3") (pin "IN2-") (pinfunction "GND_IN2-") (pintype "bidirectional"))
      (node (ref "LEDDRIVER4") (pin "IN1-") (pinfunction "GND_IN1-") (pintype "bidirectional"))
      (node (ref "LEDDRIVER4") (pin "IN2-") (pinfunction "GND_IN2-") (pintype "bidirectional"))
      (node (ref "LEDDRIVER5") (pin "IN1-") (pinfunction "GND_IN1-") (pintype "bidirectional"))
      (node (ref "LEDDRIVER5") (pin "IN2-") (pinfunction "GND_IN2-") (pintype "bidirectional"))
      (node (ref "LEDDRIVER6") (pin "IN1-") (pinfunction "GND_IN1-") (pintype "bidirectional"))
      (node (ref "LEDDRIVER6") (pin "IN2-") (pinfunction "GND_IN2-") (pintype "bidirectional"))
      (node (ref "LEDDRIVER7") (pin "IN1-") (pinfunction "GND_IN1-") (pintype "bidirectional"))
      (node (ref "LEDDRIVER7") (pin "IN2-") (pinfunction "GND_IN2-") (pintype "bidirectional"))
      (node (ref "LEDDRIVER8") (pin "IN1-") (pinfunction "GND_IN1-") (pintype "bidirectional"))
      (node (ref "LEDDRIVER8") (pin "IN2-") (pinfunction "GND_IN2-") (pintype "bidirectional"))
      (node (ref "OSC") (pin "2") (pinfunction "2_2") (pintype "passive"))
      (node (ref "Q1") (pin "3") (pinfunction "S_3") (pintype "passive"))
      (node (ref "Q2") (pin "3") (pinfunction "S_3") (pintype "passive"))
      (node (ref "Q3") (pin "3") (pinfunction "S_3") (pintype "passive"))
      (node (ref "Q4") (pin "3") (pinfunction "S_3") (pintype "passive"))
      (node (ref "Q5") (pin "3") (pinfunction "S_3") (pintype "passive"))
      (node (ref "R9") (pin "1") (pinfunction "1_1") (pintype "passive"))
      (node (ref "RN2") (pin "4") (pinfunction "1_4") (pintype "passive"))
      (node (ref "RN6") (pin "1") (pinfunction "1_1") (pintype "passive"))
      (node (ref "RN6") (pin "2") (pinfunction "1_2") (pintype "passive"))
      (node (ref "RN6") (pin "5") (pinfunction "2_5") (pintype "passive"))
      (node (ref "RN6") (pin "6") (pinfunction "2_6") (pintype "passive"))
      (node (ref "RN7") (pin "1") (pinfunction "1_1") (pintype "passive"))
      (node (ref "RN7") (pin "2") (pinfunction "1_2") (pintype "passive"))
      (node (ref "RN7") (pin "3") (pinfunction "1_3") (pintype "passive"))
      (node (ref "RN7") (pin "5") (pinfunction "2_5") (pintype "passive"))
      (node (ref "RN8") (pin "5") (pinfunction "2_5") (pintype "passive"))
      (node (ref "RN8") (pin "6") (pinfunction "2_6") (pintype "passive"))
      (node (ref "RN8") (pin "7") (pinfunction "2_7") (pintype "passive"))
      (node (ref "RN8") (pin "8") (pinfunction "2_8") (pintype "passive"))
      (node (ref "RST") (pin "A") (pinfunction "P_A") (pintype "passive"))
      (node (ref "RST") (pin "A'") (pinfunction "P1_A'") (pintype "passive"))
      (node (ref "U$1") (pin "P$1") (pinfunction "P$1_P$1") (pintype "bidirectional"))
      (node (ref "U$1") (pin "P$2") (pinfunction "P$1_P$2") (pintype "bidirectional"))
      (node (ref "U$1") (pin "P$4") (pinfunction "3_P$4") (pintype "passive"))
      (node (ref "U$2") (pin "A1") (pinfunction "GND_A1") (pintype "power_in"))
      (node (ref "U$3") (pin "2") (pinfunction "P$2_2") (pintype "bidirectional"))
      (node (ref "U$5") (pin "P$1") (pinfunction "P$1_P$1") (pintype "bidirectional"))
      (node (ref "U$6") (pin "P$1") (pinfunction "P$1_P$1") (pintype "bidirectional"))
      (node (ref "U$8") (pin "P$1") (pinfunction "GND_P$1") (pintype "bidirectional"))
      (node (ref "U$8") (pin "P$2") (pinfunction "GND_P$2") (pintype "bidirectional"))
      (node (ref "U$9") (pin "P$1") (pinfunction "P$1_P$1") (pintype "bidirectional"))
      (node (ref "U1") (pin "5") (pinfunction "GND_5") (pintype "power_in"))
      (node (ref "U2") (pin "4") (pinfunction "GND_4") (pintype "power_in"))
      (node (ref "U3") (pin "7") (pinfunction "GND_7") (pintype "power_in"))
      (node (ref "U4") (pin "4") (pinfunction "GND_4") (pintype "bidirectional"))
      (node (ref "U5") (pin "14") (pinfunction "GND_14") (pintype "power_in"))
      (node (ref "X5") (pin "9") (pinfunction "S_9") (pintype "passive"))
      (node (ref "X7") (pin "1") (pinfunction "S_1") (pintype "passive"))
    )
    (net (code "26") (name "L4") (class "Default")
      (node (ref "RN4") (pin "4") (pinfunction "1_4") (pintype "passive"))
      (node (ref "U5") (pin "10") (pinfunction "PWM4_10") (pintype "output"))
    )
    (net (code "27") (name "L5") (class "Default")
      (node (ref "RN4") (pin "3") (pinfunction "1_3") (pintype "passive"))
      (node (ref "U5") (pin "11") (pinfunction "PWM5_11") (pintype "output"))
    )
    (net (code "28") (name "L6") (class "Default")
      (node (ref "RN4") (pin "2") (pinfunction "1_2") (pintype "passive"))
      (node (ref "U5") (pin "12") (pinfunction "PWM6_12") (pintype "output"))
    )
    (net (code "29") (name "L7") (class "Default")
      (node (ref "RN4") (pin "1") (pinfunction "1_1") (pintype "passive"))
      (node (ref "U5") (pin "13") (pinfunction "PWM7_13") (pintype "output"))
    )
    (net (code "30") (name "L8") (class "Default")
      (node (ref "RN5") (pin "1") (pinfunction "1_1") (pintype "passive"))
      (node (ref "U5") (pin "15") (pinfunction "PWM8_15") (pintype "output"))
    )
    (net (code "31") (name "L9") (class "Default")
      (node (ref "RN5") (pin "2") (pinfunction "1_2") (pintype "passive"))
      (node (ref "U5") (pin "16") (pinfunction "PWM9_16") (pintype "output"))
    )
    (net (code "32") (name "L10") (class "Default")
      (node (ref "RN5") (pin "3") (pinfunction "1_3") (pintype "passive"))
      (node (ref "U5") (pin "17") (pinfunction "PWM10_17") (pintype "output"))
    )
    (net (code "33") (name "L11") (class "Default")
      (node (ref "RN5") (pin "4") (pinfunction "1_4") (pintype "passive"))
      (node (ref "U5") (pin "18") (pinfunction "PWM11_18") (pintype "output"))
    )
    (net (code "34") (name "L12") (class "Default")
      (node (ref "R7") (pin "2") (pinfunction "2_2") (pintype "passive"))
      (node (ref "U5") (pin "19") (pinfunction "PWM12_19") (pintype "output"))
    )
    (net (code "35") (name "LED1A") (class "Default")
      (node (ref "CN1") (pin "8") (pinfunction "8_8") (pintype "passive"))
      (node (ref "LEDDRIVER8") (pin "LED+") (pinfunction "LED+_LED+") (pintype "bidirectional"))
    )
    (net (code "36") (name "LED1C") (class "Default")
      (node (ref "CN1") (pin "7") (pinfunction "7_7") (pintype "passive"))
      (node (ref "LEDDRIVER8") (pin "LED-") (pinfunction "LED-_LED-") (pintype "bidirectional"))
    )
    (net (code "37") (name "LED2A") (class "Default")
      (node (ref "CN1") (pin "6") (pinfunction "6_6") (pintype "passive"))
      (node (ref "LEDDRIVER6") (pin "LED+") (pinfunction "LED+_LED+") (pintype "bidirectional"))
    )
    (net (code "38") (name "LED2C") (class "Default")
      (node (ref "CN1") (pin "5") (pinfunction "5_5") (pintype "passive"))
      (node (ref "LEDDRIVER6") (pin "LED-") (pinfunction "LED-_LED-") (pintype "bidirectional"))
    )
    (net (code "39") (name "LED3A") (class "Default")
      (node (ref "CN1") (pin "4") (pinfunction "4_4") (pintype "passive"))
      (node (ref "LEDDRIVER4") (pin "LED+") (pinfunction "LED+_LED+") (pintype "bidirectional"))
    )
    (net (code "40") (name "LED3C") (class "Default")
      (node (ref "CN1") (pin "3") (pinfunction "3_3") (pintype "passive"))
      (node (ref "LEDDRIVER4") (pin "LED-") (pinfunction "LED-_LED-") (pintype "bidirectional"))
    )
    (net (code "41") (name "LED4A") (class "Default")
      (node (ref "CN1") (pin "2") (pinfunction "2_2") (pintype "passive"))
      (node (ref "LEDDRIVER2") (pin "LED+") (pinfunction "LED+_LED+") (pintype "bidirectional"))
    )
    (net (code "42") (name "LED4C") (class "Default")
      (node (ref "CN1") (pin "1") (pinfunction "1_1") (pintype "passive"))
      (node (ref "LEDDRIVER2") (pin "LED-") (pinfunction "LED-_LED-") (pintype "bidirectional"))
    )
    (net (code "43") (name "LED5A") (class "Default")
      (node (ref "CN2") (pin "7") (pinfunction "7_7") (pintype "passive"))
      (node (ref "LEDDRIVER1") (pin "LED+") (pinfunction "LED+_LED+") (pintype "bidirectional"))
    )
    (net (code "44") (name "LED5C") (class "Default")
      (node (ref "CN2") (pin "8") (pinfunction "8_8") (pintype "passive"))
      (node (ref "LEDDRIVER1") (pin "LED-") (pinfunction "LED-_LED-") (pintype "bidirectional"))
    )
    (net (code "45") (name "LED6A") (class "Default")
      (node (ref "CN2") (pin "5") (pinfunction "5_5") (pintype "passive"))
      (node (ref "LEDDRIVER3") (pin "LED+") (pinfunction "LED+_LED+") (pintype "bidirectional"))
    )
    (net (code "46") (name "LED6C") (class "Default")
      (node (ref "CN2") (pin "6") (pinfunction "6_6") (pintype "passive"))
      (node (ref "LEDDRIVER3") (pin "LED-") (pinfunction "LED-_LED-") (pintype "bidirectional"))
    )
    (net (code "47") (name "LED7A") (class "Default")
      (node (ref "CN2") (pin "3") (pinfunction "3_3") (pintype "passive"))
      (node (ref "LEDDRIVER5") (pin "LED+") (pinfunction "LED+_LED+") (pintype "bidirectional"))
    )
    (net (code "48") (name "LED7C") (class "Default")
      (node (ref "CN2") (pin "4") (pinfunction "4_4") (pintype "passive"))
      (node (ref "LEDDRIVER5") (pin "LED-") (pinfunction "LED-_LED-") (pintype "bidirectional"))
    )
    (net (code "49") (name "LED8A") (class "Default")
      (node (ref "CN2") (pin "1") (pinfunction "1_1") (pintype "passive"))
      (node (ref "LEDDRIVER7") (pin "LED+") (pinfunction "LED+_LED+") (pintype "bidirectional"))
    )
    (net (code "50") (name "LED8C") (class "Default")
      (node (ref "CN2") (pin "2") (pinfunction "2_2") (pintype "passive"))
      (node (ref "LEDDRIVER7") (pin "LED-") (pinfunction "LED-_LED-") (pintype "bidirectional"))
    )
    (net (code "51") (name "LPWM1") (class "Default")
      (node (ref "LEDDRIVER8") (pin "PWM") (pinfunction "PWM_PWM") (pintype "bidirectional"))
      (node (ref "RN5") (pin "8") (pinfunction "2_8") (pintype "passive"))
      (node (ref "U$3") (pin "3") (pinfunction "P$3_3") (pintype "bidirectional"))
      (node (ref "X5") (pin "8") (pinfunction "S_8") (pintype "passive"))
    )
    (net (code "52") (name "LPWM2") (class "Default")
      (node (ref "LEDDRIVER6") (pin "PWM") (pinfunction "PWM_PWM") (pintype "bidirectional"))
      (node (ref "RN5") (pin "7") (pinfunction "2_7") (pintype "passive"))
      (node (ref "U$3") (pin "4") (pinfunction "P$4_4") (pintype "bidirectional"))
      (node (ref "X5") (pin "7") (pinfunction "S_7") (pintype "passive"))
    )
    (net (code "53") (name "LPWM3") (class "Default")
      (node (ref "LEDDRIVER4") (pin "PWM") (pinfunction "PWM_PWM") (pintype "bidirectional"))
      (node (ref "RN5") (pin "6") (pinfunction "2_6") (pintype "passive"))
      (node (ref "U$3") (pin "5") (pinfunction "P$5_5") (pintype "bidirectional"))
      (node (ref "X5") (pin "6") (pinfunction "S_6") (pintype "passive"))
    )
    (net (code "54") (name "LPWM4") (class "Default")
      (node (ref "LEDDRIVER2") (pin "PWM") (pinfunction "PWM_PWM") (pintype "bidirectional"))
      (node (ref "RN5") (pin "5") (pinfunction "2_5") (pintype "passive"))
      (node (ref "U$3") (pin "6") (pinfunction "P$6_6") (pintype "bidirectional"))
      (node (ref "X5") (pin "5") (pinfunction "S_5") (pintype "passive"))
    )
    (net (code "55") (name "LPWM5") (class "Default")
      (node (ref "LEDDRIVER1") (pin "PWM") (pinfunction "PWM_PWM") (pintype "bidirectional"))
      (node (ref "RN4") (pin "8") (pinfunction "2_8") (pintype "passive"))
      (node (ref "U$3") (pin "7") (pinfunction "P$7_7") (pintype "bidirectional"))
      (node (ref "X5") (pin "4") (pinfunction "S_4") (pintype "passive"))
    )
    (net (code "56") (name "LPWM6") (class "Default")
      (node (ref "LEDDRIVER3") (pin "PWM") (pinfunction "PWM_PWM") (pintype "bidirectional"))
      (node (ref "RN4") (pin "7") (pinfunction "2_7") (pintype "passive"))
      (node (ref "U$3") (pin "8") (pinfunction "P$8_8") (pintype "bidirectional"))
      (node (ref "X5") (pin "3") (pinfunction "S_3") (pintype "passive"))
    )
    (net (code "57") (name "LPWM7") (class "Default")
      (node (ref "LEDDRIVER5") (pin "PWM") (pinfunction "PWM_PWM") (pintype "bidirectional"))
      (node (ref "RN4") (pin "6") (pinfunction "2_6") (pintype "passive"))
      (node (ref "U$3") (pin "9") (pinfunction "P$9_9") (pintype "bidirectional"))
      (node (ref "X5") (pin "2") (pinfunction "S_2") (pintype "passive"))
    )
    (net (code "58") (name "LPWM8") (class "Default")
      (node (ref "LEDDRIVER7") (pin "PWM") (pinfunction "PWM_PWM") (pintype "bidirectional"))
      (node (ref "RN4") (pin "5") (pinfunction "2_5") (pintype "passive"))
      (node (ref "U$3") (pin "10") (pinfunction "P$10_10") (pintype "bidirectional"))
      (node (ref "X5") (pin "1") (pinfunction "S_1") (pintype "passive"))
    )
    (net (code "59") (name "MOSFETGND1") (class "Default")
      (node (ref "Q1") (pin "2") (pinfunction "D_2") (pintype "passive"))
      (node (ref "Q1") (pin "4") (pinfunction "D2_4") (pintype "passive"))
      (node (ref "X1") (pin "2") (pinfunction "S_2") (pintype "passive"))
    )
    (net (code "60") (name "MOSFETGND2") (class "Default")
      (node (ref "Q2") (pin "2") (pinfunction "D_2") (pintype "passive"))
      (node (ref "Q2") (pin "4") (pinfunction "D2_4") (pintype "passive"))
      (node (ref "X2") (pin "2") (pinfunction "S_2") (pintype "passive"))
    )
    (net (code "61") (name "MOSFETGND3") (class "Default")
      (node (ref "Q3") (pin "2") (pinfunction "D_2") (pintype "passive"))
      (node (ref "Q3") (pin "4") (pinfunction "D2_4") (pintype "passive"))
      (node (ref "X3") (pin "2") (pinfunction "S_2") (pintype "passive"))
    )
    (net (code "62") (name "MOSFETGND4") (class "Default")
      (node (ref "Q4") (pin "2") (pinfunction "D_2") (pintype "passive"))
      (node (ref "Q4") (pin "4") (pinfunction "D2_4") (pintype "passive"))
      (node (ref "X4") (pin "2") (pinfunction "S_2") (pintype "passive"))
    )
    (net (code "63") (name "MOSFETPWM1") (class "Default")
      (node (ref "Q1") (pin "1") (pinfunction "G_1") (pintype "passive"))
      (node (ref "RN3") (pin "1") (pinfunction "1_1") (pintype "passive"))
    )
    (net (code "64") (name "MOSFETPWM2") (class "Default")
      (node (ref "Q2") (pin "1") (pinfunction "G_1") (pintype "passive"))
      (node (ref "RN3") (pin "2") (pinfunction "1_2") (pintype "passive"))
    )
    (net (code "65") (name "MOSFETPWM3") (class "Default")
      (node (ref "Q3") (pin "1") (pinfunction "G_1") (pintype "passive"))
      (node (ref "RN3") (pin "3") (pinfunction "1_3") (pintype "passive"))
    )
    (net (code "66") (name "MOSFETPWM4") (class "Default")
      (node (ref "Q4") (pin "1") (pinfunction "G_1") (pintype "passive"))
      (node (ref "RN3") (pin "4") (pinfunction "1_4") (pintype "passive"))
    )
    (net (code "67") (name "Net-(ERROR-PadC)") (class "Default")
      (node (ref "ERROR") (pin "C") (pinfunction "C_C") (pintype "passive"))
      (node (ref "R5") (pin "1") (pinfunction "1_1") (pintype "passive"))
    )
    (net (code "68") (name "Net-(R2-Pad1)") (class "Default")
      (node (ref "R2") (pin "1") (pinfunction "1_1") (pintype "passive"))
      (node (ref "STATUS") (pin "C") (pinfunction "C_C") (pintype "passive"))
    )
    (net (code "69") (name "Net-(RN2-Pad1)") (class "Default")
      (node (ref "RN2") (pin "1") (pinfunction "1_1") (pintype "passive"))
      (node (ref "TEMP") (pin "C") (pinfunction "C_C") (pintype "passive"))
    )
    (net (code "70") (name "Net-(RN2A-2)") (class "Default")
      (node (ref "RN2") (pin "8") (pinfunction "2_8") (pintype "passive"))
      (node (ref "U2") (pin "3") (pinfunction "OS_3") (pintype "bidirectional"))
    )
    (net (code "71") (name "Net-(RN2B-1)") (class "Default")
      (node (ref "RN2") (pin "2") (pinfunction "1_2") (pintype "passive"))
      (node (ref "WTACH") (pin "C") (pinfunction "C_C") (pintype "passive"))
    )
    (net (code "72") (name "Net-(RN2B-2)") (class "Default")
      (node (ref "RN2") (pin "7") (pinfunction "2_7") (pintype "passive"))
      (node (ref "U4") (pin "3") (pinfunction "ALARM_3") (pintype "bidirectional"))
    )
    (net (code "73") (name "Net-(RN2C-1)") (class "Default")
      (node (ref "RN2") (pin "3") (pinfunction "1_3") (pintype "passive"))
      (node (ref "WTEMP") (pin "C") (pinfunction "C_C") (pintype "passive"))
    )
    (net (code "74") (name "Net-(RN2C-2)") (class "Default")
      (node (ref "RN2") (pin "6") (pinfunction "2_6") (pintype "passive"))
      (node (ref "U3") (pin "2") (pinfunction "ALERT_2") (pintype "output"))
    )
    (net (code "75") (name "Net-(RN2D-2)") (class "Default")
      (node (ref "POWER") (pin "C") (pinfunction "C_C") (pintype "passive"))
      (node (ref "RN2") (pin "5") (pinfunction "2_5") (pintype "passive"))
    )
    (net (code "76") (name "Net-(U1-FAN)") (class "Default")
      (node (ref "R11") (pin "2") (pinfunction "2_2") (pintype "passive"))
      (node (ref "R8") (pin "1") (pinfunction "1_1") (pintype "passive"))
      (node (ref "U1") (pin "4") (pinfunction "FAN_4") (pintype "output"))
    )
    (net (code "77") (name "OE") (class "Default")
      (node (ref "RN6") (pin "7") (pinfunction "2_7") (pintype "passive"))
      (node (ref "U5") (pin "23") (pinfunction "#OE_23") (pintype "input"))
    )
    (net (code "78") (name "RST") (class "Default")
      (node (ref "RN1") (pin "3") (pinfunction "1_3") (pintype "passive"))
      (node (ref "RST") (pin "B") (pinfunction "S_B") (pintype "passive"))
      (node (ref "RST") (pin "B'") (pinfunction "S1_B'") (pintype "passive"))
      (node (ref "U$1") (pin "P$3") (pinfunction "1_P$3") (pintype "passive"))
      (node (ref "U$2") (pin "C2") (pinfunction "RST_C2") (pintype "bidirectional"))
    )
    (net (code "79") (name "RX") (class "Default")
      (node (ref "U$2") (pin "D1") (pinfunction "URXD_D1") (pintype "bidirectional"))
    )
    (net (code "80") (name "SCL") (class "Default")
      (node (ref "CONN1") (pin "4") (pinfunction "SCL_4") (pintype "passive"))
      (node (ref "CONN2") (pin "4") (pinfunction "SCL_4") (pintype "passive"))
      (node (ref "IC1") (pin "6") (pinfunction "BUS1_6") (pintype "bidirectional"))
      (node (ref "J7") (pin "1") (pinfunction "1_1") (pintype "passive"))
      (node (ref "K1") (pin "2") (pinfunction "2_2") (pintype "passive"))
      (node (ref "R3") (pin "2") (pinfunction "2_2") (pintype "passive"))
      (node (ref "U$2") (pin "B1") (pinfunction "GPIO2_B1") (pintype "bidirectional"))
      (node (ref "U1") (pin "8") (pinfunction "SCL_8") (pintype "bidirectional"))
      (node (ref "U2") (pin "2") (pinfunction "SCL_2") (pintype "bidirectional"))
      (node (ref "U3") (pin "1") (pinfunction "SCL_1") (pintype "input"))
      (node (ref "U4") (pin "5") (pinfunction "SCL_5") (pintype "bidirectional"))
      (node (ref "U5") (pin "26") (pinfunction "SCL_26") (pintype "bidirectional"))
    )
    (net (code "81") (name "SDA") (class "Default")
      (node (ref "CONN1") (pin "3") (pinfunction "SDA_3") (pintype "passive"))
      (node (ref "CONN2") (pin "3") (pinfunction "SDA_3") (pintype "passive"))
      (node (ref "IC1") (pin "4") (pinfunction "BUS2_4") (pintype "bidirectional"))
      (node (ref "J7") (pin "2") (pinfunction "2_2") (pintype "passive"))
      (node (ref "K1") (pin "1") (pinfunction "1_1") (pintype "passive"))
      (node (ref "R4") (pin "2") (pinfunction "2_2") (pintype "passive"))
      (node (ref "U$2") (pin "C1") (pinfunction "GPIO0_C1") (pintype "bidirectional"))
      (node (ref "U1") (pin "7") (pinfunction "SDA_7") (pintype "bidirectional"))
      (node (ref "U2") (pin "1") (pinfunction "SDA_1") (pintype "bidirectional"))
      (node (ref "U3") (pin "8") (pinfunction "SDA_8") (pintype "bidirectional"))
      (node (ref "U4") (pin "6") (pinfunction "SDA_6") (pintype "bidirectional"))
      (node (ref "U5") (pin "27") (pinfunction "SDA_27") (pintype "bidirectional"))
    )
    (net (code "82") (name "SERVOPWM") (class "Default")
      (node (ref "J4") (pin "3") (pinfunction "3_3") (pintype "passive"))
      (node (ref "R7") (pin "1") (pinfunction "1_1") (pintype "passive"))
    )
    (net (code "83") (name "TA0") (class "Default")
      (node (ref "A9") (pin "2") (pinfunction "2_2") (pintype "passive"))
      (node (ref "RN7") (pin "6") (pinfunction "2_6") (pintype "passive"))
      (node (ref "U2") (pin "7") (pinfunction "A0_7") (pintype "bidirectional"))
    )
    (net (code "84") (name "TA1") (class "Default")
      (node (ref "A4") (pin "2") (pinfunction "2_2") (pintype "passive"))
      (node (ref "RN7") (pin "7") (pinfunction "2_7") (pintype "passive"))
      (node (ref "U2") (pin "6") (pinfunction "A1_6") (pintype "bidirectional"))
    )
    (net (code "85") (name "TA2") (class "Default")
      (node (ref "A5") (pin "2") (pinfunction "2_2") (pintype "passive"))
      (node (ref "RN7") (pin "8") (pinfunction "2_8") (pintype "passive"))
      (node (ref "U2") (pin "5") (pinfunction "A2_5") (pintype "bidirectional"))
    )
    (net (code "86") (name "TURBINETACH") (class "Default")
      (node (ref "R10") (pin "2") (pinfunction "2_2") (pintype "passive"))
      (node (ref "U4") (pin "1") (pinfunction "EVENT_1") (pintype "bidirectional"))
      (node (ref "X7") (pin "2") (pinfunction "S_2") (pintype "passive"))
    )
    (net (code "87") (name "TURBINETHERM") (class "Default")
      (node (ref "R9") (pin "2") (pinfunction "2_2") (pintype "passive"))
      (node (ref "U3") (pin "4") (pinfunction "VIN_4") (pintype "input"))
      (node (ref "X6") (pin "2") (pinfunction "S_2") (pintype "passive"))
    )
    (net (code "88") (name "TX") (class "Default")
      (node (ref "U$2") (pin "A2") (pinfunction "UTXD_A2") (pintype "bidirectional"))
    )
    (net (code "89") (name "VCC1") (class "Default")
      (node (ref "$$U$7") (pin "P$1") (pinfunction "P$1_P$1") (pintype "bidirectional"))
      (node (ref "C5") (pin "1") (pinfunction "1_1") (pintype "passive"))
      (node (ref "C6") (pin "2") (pinfunction "2_2") (pintype "passive"))
      (node (ref "DD4012SA") (pin "1") (pinfunction "1_1") (pintype "passive"))
      (node (ref "J2") (pin "2") (pinfunction "2_2") (pintype "passive"))
      (node (ref "J4") (pin "2") (pinfunction "2_2") (pintype "passive"))
      (node (ref "JP1") (pin "1") (pinfunction "1_1") (pintype "passive"))
      (node (ref "JP3") (pin "1") (pinfunction "1_1") (pintype "passive"))
      (node (ref "LEDDRIVER2") (pin "IN1+") (pinfunction "VCC_IN1+") (pintype "bidirectional"))
      (node (ref "LEDDRIVER2") (pin "IN2+") (pinfunction "VCC_IN2+") (pintype "bidirectional"))
      (node (ref "LEDDRIVER4") (pin "IN1+") (pinfunction "VCC_IN1+") (pintype "bidirectional"))
      (node (ref "LEDDRIVER4") (pin "IN2+") (pinfunction "VCC_IN2+") (pintype "bidirectional"))
      (node (ref "LEDDRIVER6") (pin "IN1+") (pinfunction "VCC_IN1+") (pintype "bidirectional"))
      (node (ref "LEDDRIVER6") (pin "IN2+") (pinfunction "VCC_IN2+") (pintype "bidirectional"))
      (node (ref "LEDDRIVER8") (pin "IN1+") (pinfunction "VCC_IN1+") (pintype "bidirectional"))
      (node (ref "LEDDRIVER8") (pin "IN2+") (pinfunction "VCC_IN2+") (pintype "bidirectional"))
      (node (ref "U$8") (pin "P$3") (pinfunction "VUSBPD_P$3") (pintype "bidirectional"))
      (node (ref "U$8") (pin "P$4") (pinfunction "VUSBPD_P$4") (pintype "bidirectional"))
    )
    (net (code "90") (name "VCC2") (class "Default")
      (node (ref "C7") (pin "1") (pinfunction "1_1") (pintype "passive"))
      (node (ref "C8") (pin "2") (pinfunction "2_2") (pintype "passive"))
      (node (ref "J6") (pin "1") (pinfunction "1_1") (pintype "passive"))
      (node (ref "JP2") (pin "2") (pinfunction "2_2") (pintype "passive"))
      (node (ref "JP3") (pin "2") (pinfunction "2_2") (pintype "passive"))
      (node (ref "LEDDRIVER1") (pin "IN1+") (pinfunction "VCC_IN1+") (pintype "bidirectional"))
      (node (ref "LEDDRIVER1") (pin "IN2+") (pinfunction "VCC_IN2+") (pintype "bidirectional"))
      (node (ref "LEDDRIVER3") (pin "IN1+") (pinfunction "VCC_IN1+") (pintype "bidirectional"))
      (node (ref "LEDDRIVER3") (pin "IN2+") (pinfunction "VCC_IN2+") (pintype "bidirectional"))
      (node (ref "LEDDRIVER5") (pin "IN1+") (pinfunction "VCC_IN1+") (pintype "bidirectional"))
      (node (ref "LEDDRIVER5") (pin "IN2+") (pinfunction "VCC_IN2+") (pintype "bidirectional"))
      (node (ref "LEDDRIVER7") (pin "IN1+") (pinfunction "VCC_IN1+") (pintype "bidirectional"))
      (node (ref "LEDDRIVER7") (pin "IN2+") (pinfunction "VCC_IN2+") (pintype "bidirectional"))
      (node (ref "U$10") (pin "P$1") (pinfunction "P$1_P$1") (pintype "bidirectional"))
    )
    (net (code "91") (name "VCC3") (class "Default")
      (node (ref "C2") (pin "2") (pinfunction "2_2") (pintype "passive"))
      (node (ref "C4") (pin "1") (pinfunction "1_1") (pintype "passive"))
      (node (ref "J1") (pin "2") (pinfunction "2_2") (pintype "passive"))
      (node (ref "J3") (pin "2") (pinfunction "2_2") (pintype "passive"))
      (node (ref "JP1") (pin "2") (pinfunction "2_2") (pintype "passive"))
      (node (ref "JP2") (pin "1") (pinfunction "1_1") (pintype "passive"))
      (node (ref "U$4") (pin "P$1") (pinfunction "P$1_P$1") (pintype "bidirectional"))
      (node (ref "X1") (pin "1") (pinfunction "S_1") (pintype "passive"))
      (node (ref "X2") (pin "1") (pinfunction "S_1") (pintype "passive"))
      (node (ref "X3") (pin "1") (pinfunction "S_1") (pintype "passive"))
      (node (ref "X4") (pin "1") (pinfunction "S_1") (pintype "passive"))
    )
    (net (code "92") (name "unconnected-(CONN1A-GND-Pad1)") (class "Default")
      (node (ref "CONN1") (pin "1") (pinfunction "GND_1") (pintype "passive"))
    )
    (net (code "93") (name "unconnected-(RN1B-1-Pad2)") (class "Default")
      (node (ref "RN1") (pin "2") (pinfunction "1_2") (pintype "passive"))
    )
    (net (code "94") (name "unconnected-(RN1B-2-Pad7)") (class "Default")
      (node (ref "RN1") (pin "7") (pinfunction "2_7") (pintype "passive"))
    )
    (net (code "95") (name "unconnected-(U$3-PadMT1)") (class "Default")
      (node (ref "U$3") (pin "MT1") (pinfunction "MT1_MT1") (pintype "bidirectional"))
    )
    (net (code "96") (name "unconnected-(U$3-PadMT2)") (class "Default")
      (node (ref "U$3") (pin "MT2") (pinfunction "MT2_MT2") (pintype "bidirectional"))
    )
  )
)
